# Board_V1.net
KiCad netlist of a schematic drawn in EAGLE
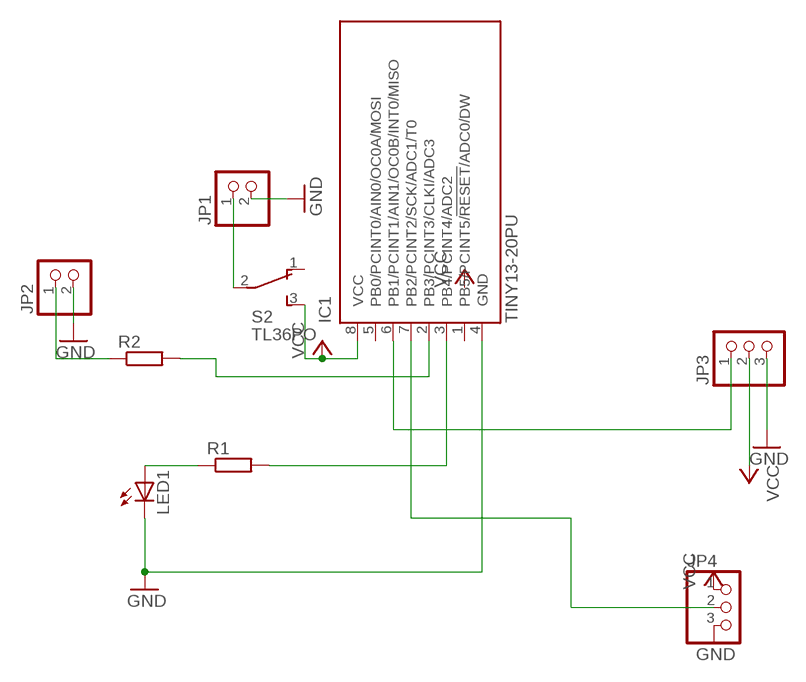
[diagram p0: schematic, sheet 1]

(export (version "E")
  (design (tool "Eeschema 10.0.6"))
  (components
    (comp (ref "IC1")
      (value "TINY13-20PU")
      (footprint "eagle-import:DIL08")
      (fields (field (name "MPN") "ATTINY13-20PU"))
      (libsource (lib "eagle-import") (part "TINY13PU-20"))
    )
    (comp (ref "JP1")
      (value "PINHD-1X2")
      (footprint "eagle-import:1X02")
      (libsource (lib "eagle-import") (part "PINHD-1X2"))
    )
    (comp (ref "JP2")
      (value "PINHD-1X2")
      (footprint "eagle-import:1X02")
      (libsource (lib "eagle-import") (part "PINHD-1X2"))
    )
    (comp (ref "JP3")
      (value "PINHD-1X3")
      (footprint "eagle-import:1X03")
      (libsource (lib "eagle-import") (part "PINHD-1X3"))
    )
    (comp (ref "JP4")
      (value "PINHD-1X3")
      (footprint "eagle-import:1X03")
      (libsource (lib "eagle-import") (part "PINHD-1X3"))
    )
    (comp (ref "LED1")
      (value "LED5MM")
      (footprint "eagle-import:LED5MM")
      (libsource (lib "eagle-import") (part "LED5MM"))
    )
    (comp (ref "R1")
      (value "R-EU_0204/7")
      (footprint "eagle-import:0204_7")
      (libsource (lib "eagle-import") (part "R-EU_0204/7"))
    )
    (comp (ref "R2")
      (value "R-EU_0204/7")
      (footprint "eagle-import:0204_7")
      (libsource (lib "eagle-import") (part "R-EU_0204/7"))
    )
    (comp (ref "S2")
      (value "TL36PO")
      (footprint "eagle-import:TL3XPO")
      (libsource (lib "eagle-import") (part "TL36PO"))
    )
  )
  (nets
    (net (code "1") (name "GND") (class "Default")
      (node (ref "IC1") (pin "4") (pinfunction "GND_4") (pintype "power_in"))
      (node (ref "JP1") (pin "2") (pinfunction "2_2") (pintype "passive"))
      (node (ref "JP2") (pin "2") (pinfunction "2_2") (pintype "passive"))
      (node (ref "JP3") (pin "3") (pinfunction "3_3") (pintype "passive"))
      (node (ref "JP4") (pin "3") (pinfunction "3_3") (pintype "passive"))
      (node (ref "LED1") (pin "K") (pinfunction "C_K") (pintype "passive"))
    )
    (net (code "2") (name "Net-(IC1-PB1{slash}PCINT1{slash}AIN1{slash}OC0B{slash}INT0{slash}MISO)") (class "Default")
      (node (ref "IC1") (pin "6") (pinfunction "PB1/PCINT1/AIN1/OC0B/INT0/MISO_6") (pintype "bidirectional"))
      (node (ref "JP3") (pin "1") (pinfunction "1_1") (pintype "passive"))
    )
    (net (code "3") (name "Net-(IC1-PB2{slash}PCINT2{slash}SCK{slash}ADC1{slash}T0)") (class "Default")
      (node (ref "IC1") (pin "7") (pinfunction "PB2/PCINT2/SCK/ADC1/T0_7") (pintype "bidirectional"))
      (node (ref "JP4") (pin "2") (pinfunction "2_2") (pintype "passive"))
    )
    (net (code "4") (name "Net-(IC1-PB3{slash}PCINT3{slash}CLKI{slash}ADC3)") (class "Default")
      (node (ref "IC1") (pin "2") (pinfunction "PB3/PCINT3/CLKI/ADC3_2") (pintype "bidirectional"))
      (node (ref "R2") (pin "2") (pinfunction "2_2") (pintype "passive"))
    )
    (net (code "5") (name "Net-(IC1-PB4{slash}PCINT4{slash}ADC2)") (class "Default")
      (node (ref "IC1") (pin "3") (pinfunction "PB4/PCINT4/ADC2_3") (pintype "bidirectional"))
      (node (ref "R1") (pin "2") (pinfunction "2_2") (pintype "passive"))
    )
    (net (code "6") (name "Net-(JP2-Pad1)") (class "Default")
      (node (ref "JP2") (pin "1") (pinfunction "1_1") (pintype "passive"))
      (node (ref "R2") (pin "1") (pinfunction "1_1") (pintype "passive"))
    )
    (net (code "7") (name "Net-(LED1-PadA)") (class "Default")
      (node (ref "LED1") (pin "A") (pinfunction "A_A") (pintype "passive"))
      (node (ref "R1") (pin "1") (pinfunction "1_1") (pintype "passive"))
    )
    (net (code "8") (name "Net-(S2-P)") (class "Default")
      (node (ref "JP1") (pin "1") (pinfunction "1_1") (pintype "passive"))
      (node (ref "S2") (pin "2") (pinfunction "P_2") (pintype "passive"))
    )
    (net (code "9") (name "VCC") (class "Default")
      (node (ref "IC1") (pin "8") (pinfunction "VCC_8") (pintype "power_in"))
      (node (ref "JP3") (pin "2") (pinfunction "2_2") (pintype "passive"))
      (node (ref "JP4") (pin "1") (pinfunction "1_1") (pintype "passive"))
      (node (ref "S2") (pin "3") (pinfunction "S_3") (pintype "passive"))
    )
    (net (code "10") (name "unconnected-(IC1-PB0{slash}PCINT0{slash}AIN0{slash}OC0A{slash}MOSI-Pad5)") (class "Default")
      (node (ref "IC1") (pin "5") (pinfunction "PB0/PCINT0/AIN0/OC0A/MOSI_5") (pintype "bidirectional"))
    )
    (net (code "11") (name "unconnected-(IC1-PB5{slash}PCINT5{slash}~{RESET}{slash}ADC0{slash}DW-Pad1)") (class "Default")
      (node (ref "IC1") (pin "1") (pinfunction "PB5/PCINT5/~{RESET}/ADC0/DW_1") (pintype "bidirectional"))
    )
    (net (code "12") (name "unconnected-(S2-O-Pad1)") (class "Default")
      (node (ref "S2") (pin "1") (pinfunction "O_1") (pintype "passive"))
    )
  )
)
